# valve_gpio.net
KiCad netlist of a schematic drawn in Altium Designer
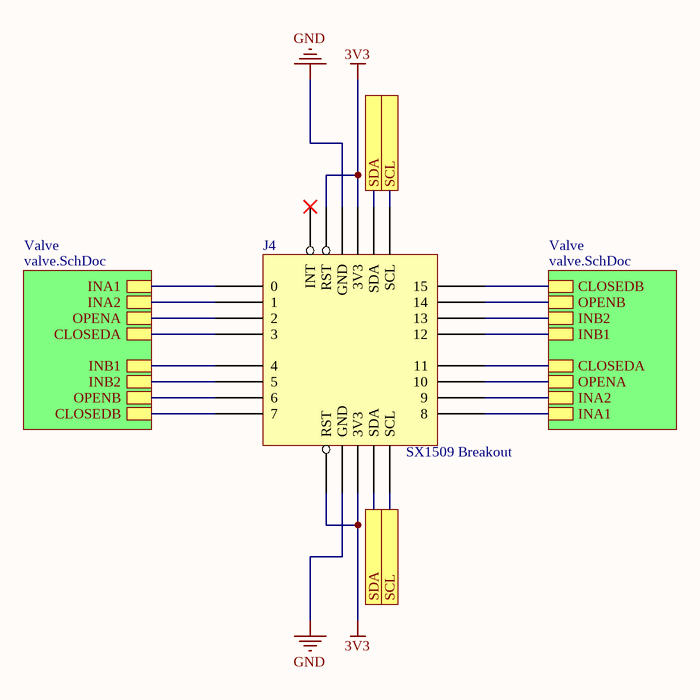
[diagram p0: valve_gpio.SchDoc]

(export (version "E")
  (design (tool "Eeschema 10.0.6"))
  (components
    (comp (ref "J4")
      (value "SX1509 Breakout")
      (footprint "SX1509 Breakout")
      (libsource (lib "brew_lib") (part "SX1509 Breakout"))
    )
  )
  (nets
    (net (code "1") (name "/CLOSEDA") (class "Default")
      (node (ref "J4") (pin "17") (pinfunction "11_17") (pintype "passive"))
    )
    (net (code "2") (name "/CLOSEDA_1") (class "Default")
      (node (ref "J4") (pin "4") (pinfunction "3_4") (pintype "passive"))
    )
    (net (code "3") (name "/CLOSEDB") (class "Default")
      (node (ref "J4") (pin "21") (pinfunction "15_21") (pintype "passive"))
    )
    (net (code "4") (name "/CLOSEDB_1") (class "Default")
      (node (ref "J4") (pin "8") (pinfunction "7_8") (pintype "passive"))
    )
    (net (code "5") (name "/INA1") (class "Default")
      (node (ref "J4") (pin "14") (pinfunction "8_14") (pintype "passive"))
    )
    (net (code "6") (name "/INA1_1") (class "Default")
      (node (ref "J4") (pin "1") (pinfunction "0_1") (pintype "passive"))
    )
    (net (code "7") (name "/INA2") (class "Default")
      (node (ref "J4") (pin "15") (pinfunction "9_15") (pintype "passive"))
    )
    (net (code "8") (name "/INA2_1") (class "Default")
      (node (ref "J4") (pin "2") (pinfunction "1_2") (pintype "passive"))
    )
    (net (code "9") (name "/INB1") (class "Default")
      (node (ref "J4") (pin "18") (pinfunction "12_18") (pintype "passive"))
    )
    (net (code "10") (name "/INB1_1") (class "Default")
      (node (ref "J4") (pin "5") (pinfunction "4_5") (pintype "passive"))
    )
    (net (code "11") (name "/INB2") (class "Default")
      (node (ref "J4") (pin "19") (pinfunction "13_19") (pintype "passive"))
    )
    (net (code "12") (name "/INB2_1") (class "Default")
      (node (ref "J4") (pin "6") (pinfunction "5_6") (pintype "passive"))
    )
    (net (code "13") (name "/OPENA") (class "Default")
      (node (ref "J4") (pin "16") (pinfunction "10_16") (pintype "passive"))
    )
    (net (code "14") (name "/OPENA_1") (class "Default")
      (node (ref "J4") (pin "3") (pinfunction "2_3") (pintype "passive"))
    )
    (net (code "15") (name "/OPENB") (class "Default")
      (node (ref "J4") (pin "20") (pinfunction "14_20") (pintype "passive"))
    )
    (net (code "16") (name "/OPENB_1") (class "Default")
      (node (ref "J4") (pin "7") (pinfunction "6_7") (pintype "passive"))
    )
    (net (code "17") (name "/SCL") (class "Default")
      (node (ref "J4") (pin "13") (pinfunction "SCL_13") (pintype "passive"))
      (node (ref "J4") (pin "22") (pinfunction "SCL_22") (pintype "passive"))
    )
    (net (code "18") (name "/SDA") (class "Default")
      (node (ref "J4") (pin "12") (pinfunction "SDA_12") (pintype "passive"))
      (node (ref "J4") (pin "23") (pinfunction "SDA_23") (pintype "passive"))
    )
    (net (code "19") (name "3V3") (class "Default")
      (node (ref "J4") (pin "11") (pinfunction "3V3_11") (pintype "passive"))
      (node (ref "J4") (pin "24") (pinfunction "3V3_24") (pintype "passive"))
      (node (ref "J4") (pin "26") (pinfunction "RST_26") (pintype "passive"))
      (node (ref "J4") (pin "9") (pinfunction "RST_9") (pintype "passive"))
    )
    (net (code "20") (name "GND") (class "Default")
      (node (ref "J4") (pin "10") (pinfunction "GND_10") (pintype "passive"))
      (node (ref "J4") (pin "25") (pinfunction "GND_25") (pintype "passive"))
    )
    (net (code "21") (name "unconnected-(J4-INT-Pad27)") (class "Default")
      (node (ref "J4") (pin "27") (pinfunction "INT_27") (pintype "passive+no_connect"))
    )
  )
)
